# pmd_final.net
KiCad netlist of a schematic drawn in EAGLE
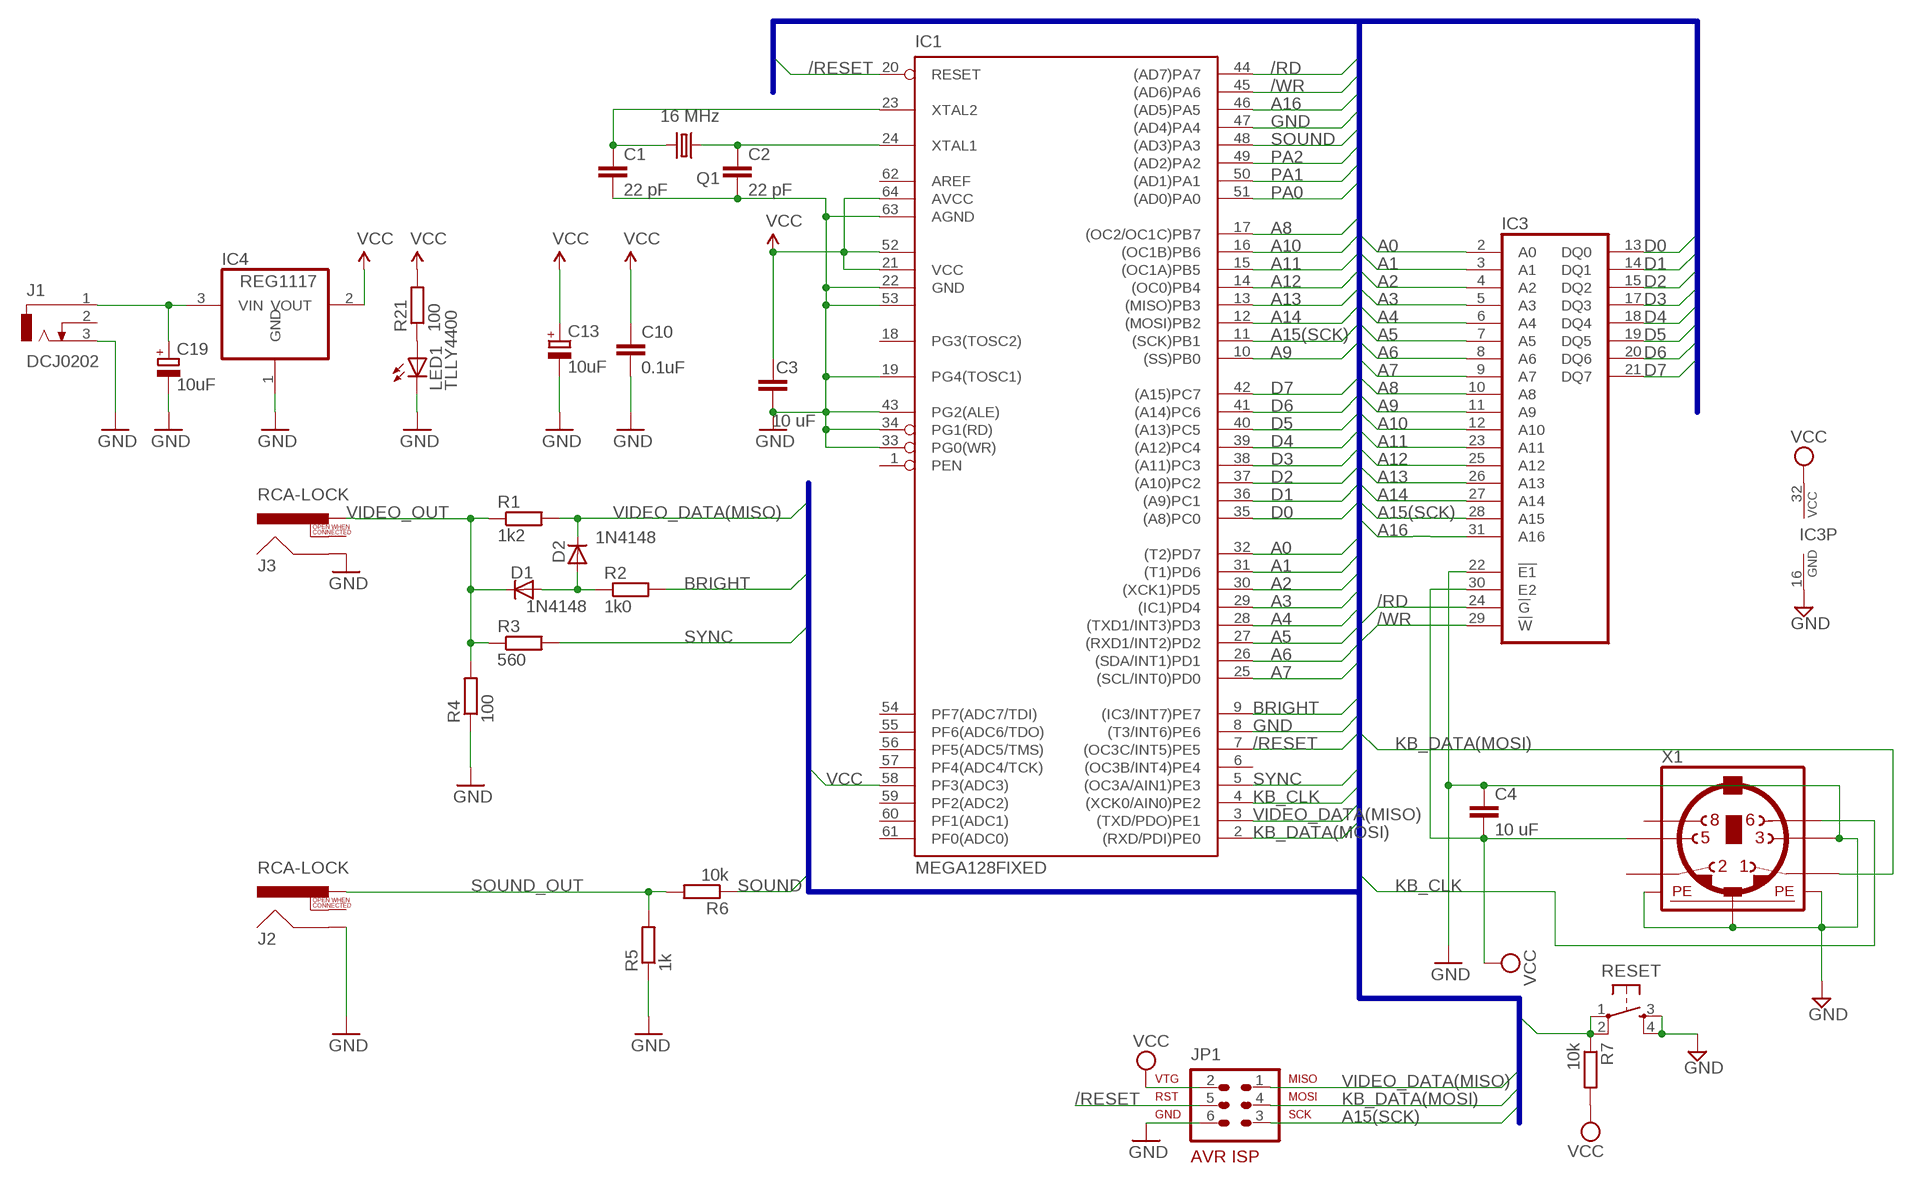
[diagram p0: schematic, sheet 1]

(export (version "E")
  (design (tool "Eeschema 10.0.6"))
  (components
    (comp (ref "C1")
      (value "22 pF")
      (footprint "eagle-import:C0805")
      (libsource (lib "eagle-import") (part "C-EUC0805"))
    )
    (comp (ref "C2")
      (value "22 pF")
      (footprint "eagle-import:C0805")
      (libsource (lib "eagle-import") (part "C-EUC0805"))
    )
    (comp (ref "C3")
      (value "10 uF")
      (footprint "eagle-import:C0805")
      (libsource (lib "eagle-import") (part "C-EUC0805"))
    )
    (comp (ref "C4")
      (value "10 uF")
      (footprint "eagle-import:C0805")
      (libsource (lib "eagle-import") (part "C-EUC0805"))
    )
    (comp (ref "C10")
      (value "0.1uF")
      (footprint "eagle-import:C0805")
      (libsource (lib "eagle-import") (part "C-EUC0805"))
    )
    (comp (ref "C13")
      (value "10uF")
      (footprint "eagle-import:E2,5-5")
      (libsource (lib "eagle-import") (part "CPOL-EUE2.5-5"))
    )
    (comp (ref "C19")
      (value "10uF")
      (footprint "eagle-import:E2,5-5")
      (libsource (lib "eagle-import") (part "CPOL-EUE2.5-5"))
    )
    (comp (ref "D1")
      (value "1N4148")
      (footprint "eagle-import:MINIMELF")
      (libsource (lib "eagle-import") (part "DIODE-MINIMELF"))
    )
    (comp (ref "D2")
      (value "1N4148")
      (footprint "eagle-import:MINIMELF")
      (libsource (lib "eagle-import") (part "DIODE-MINIMELF"))
    )
    (comp (ref "IC1")
      (value "MEGA128FIXED")
      (footprint "eagle-import:TQFP64_14X14MM")
      (libsource (lib "eagle-import") (part "MEGA128FIXED"))
    )
    (comp (ref "IC3")
      (value "MCM6226AULTRAWIDE")
      (footprint "eagle-import:SOP32L")
      (libsource (lib "eagle-import") (part "MCM6226AULTRAWIDE"))
    )
    (comp (ref "IC4")
      (value "REG1117")
      (footprint "eagle-import:SOT223")
      (libsource (lib "eagle-import") (part "REG1117"))
    )
    (comp (ref "J1")
      (value "DCJ0202")
      (footprint "eagle-import:DCJ0202")
      (libsource (lib "eagle-import") (part "DCJ0202"))
    )
    (comp (ref "J2")
      (value "RCA-LOCK")
      (footprint "eagle-import:RCA_LOCK")
      (libsource (lib "eagle-import") (part "RCA-LOCK"))
    )
    (comp (ref "J3")
      (value "RCA-LOCK")
      (footprint "eagle-import:RCA_LOCK")
      (libsource (lib "eagle-import") (part "RCA-LOCK"))
    )
    (comp (ref "JP1")
      (value "AVR-ISP-6R")
      (footprint "eagle-import:AVR-ISP-6R")
      (libsource (lib "eagle-import") (part "AVR-ISP-6R"))
    )
    (comp (ref "LED1")
      (value "TLLY4400")
      (footprint "eagle-import:LED3MM")
      (fields (field (name "MF") "VISHAY SEMICONDUCTOR"))
      (libsource (lib "eagle-import") (part "TLLY4400"))
    )
    (comp (ref "Q1")
      (value "16 MHz")
      (footprint "eagle-import:HC49UP")
      (libsource (lib "eagle-import") (part "CRYSTALHC49UP"))
    )
    (comp (ref "R1")
      (value "1k2")
      (footprint "eagle-import:R0805")
      (libsource (lib "eagle-import") (part "R-EU_R0805"))
    )
    (comp (ref "R2")
      (value "1k0")
      (footprint "eagle-import:R0805")
      (libsource (lib "eagle-import") (part "R-EU_R0805"))
    )
    (comp (ref "R3")
      (value "560")
      (footprint "eagle-import:R0805")
      (libsource (lib "eagle-import") (part "R-EU_R0805"))
    )
    (comp (ref "R4")
      (value "100")
      (footprint "eagle-import:R0805")
      (libsource (lib "eagle-import") (part "R-EU_R0805"))
    )
    (comp (ref "R5")
      (value "1k")
      (footprint "eagle-import:R0805")
      (libsource (lib "eagle-import") (part "R-EU_R0805"))
    )
    (comp (ref "R6")
      (value "10k")
      (footprint "eagle-import:R0805")
      (libsource (lib "eagle-import") (part "R-EU_R0805"))
    )
    (comp (ref "R7")
      (value "10k")
      (footprint "eagle-import:R0805")
      (libsource (lib "eagle-import") (part "R-EU_R0805"))
    )
    (comp (ref "R21")
      (value "100")
      (footprint "eagle-import:R0805")
      (libsource (lib "eagle-import") (part "R-EU_R0805"))
    )
    (comp (ref "RESET")
      (value "RESET")
      (footprint "eagle-import:TACTILE-PTH")
      (libsource (lib "eagle-import") (part "TAC_SWITCHPTH"))
    )
    (comp (ref "X1")
      (value "MINI_DIN_6")
      (footprint "eagle-import:M_DIN6")
      (libsource (lib "eagle-import") (part "MINI_DIN_6"))
    )
  )
  (nets
    (net (code "1") (name "/A0") (class "Default")
      (node (ref "IC1") (pin "32") (pinfunction "(T2)PD7_32") (pintype "bidirectional"))
      (node (ref "IC3") (pin "2") (pinfunction "A0_2") (pintype "input"))
    )
    (net (code "2") (name "/A1") (class "Default")
      (node (ref "IC1") (pin "31") (pinfunction "(T1)PD6_31") (pintype "bidirectional"))
      (node (ref "IC3") (pin "3") (pinfunction "A1_3") (pintype "input"))
    )
    (net (code "3") (name "/A2") (class "Default")
      (node (ref "IC1") (pin "30") (pinfunction "(XCK1)PD5_30") (pintype "bidirectional"))
      (node (ref "IC3") (pin "4") (pinfunction "A2_4") (pintype "input"))
    )
    (net (code "4") (name "/A3") (class "Default")
      (node (ref "IC1") (pin "29") (pinfunction "(IC1)PD4_29") (pintype "bidirectional"))
      (node (ref "IC3") (pin "5") (pinfunction "A3_5") (pintype "input"))
    )
    (net (code "5") (name "/A4") (class "Default")
      (node (ref "IC1") (pin "28") (pinfunction "(TXD1/INT3)PD3_28") (pintype "bidirectional"))
      (node (ref "IC3") (pin "6") (pinfunction "A4_6") (pintype "input"))
    )
    (net (code "6") (name "/A5") (class "Default")
      (node (ref "IC1") (pin "27") (pinfunction "(RXD1/INT2)PD2_27") (pintype "bidirectional"))
      (node (ref "IC3") (pin "7") (pinfunction "A5_7") (pintype "input"))
    )
    (net (code "7") (name "/A6") (class "Default")
      (node (ref "IC1") (pin "26") (pinfunction "(SDA/INT1)PD1_26") (pintype "bidirectional"))
      (node (ref "IC3") (pin "8") (pinfunction "A6_8") (pintype "input"))
    )
    (net (code "8") (name "/A7") (class "Default")
      (node (ref "IC1") (pin "25") (pinfunction "(SCL/INT0)PD0_25") (pintype "bidirectional"))
      (node (ref "IC3") (pin "9") (pinfunction "A7_9") (pintype "input"))
    )
    (net (code "9") (name "/A8") (class "Default")
      (node (ref "IC1") (pin "17") (pinfunction "(OC2/OC1C)PB7_17") (pintype "bidirectional"))
      (node (ref "IC3") (pin "10") (pinfunction "A8_10") (pintype "input"))
    )
    (net (code "10") (name "/A9") (class "Default")
      (node (ref "IC1") (pin "10") (pinfunction "(SS)PB0_10") (pintype "bidirectional"))
      (node (ref "IC3") (pin "11") (pinfunction "A9_11") (pintype "input"))
    )
    (net (code "11") (name "/A10") (class "Default")
      (node (ref "IC1") (pin "16") (pinfunction "(OC1B)PB6_16") (pintype "bidirectional"))
      (node (ref "IC3") (pin "12") (pinfunction "A10_12") (pintype "input"))
    )
    (net (code "12") (name "/A11") (class "Default")
      (node (ref "IC1") (pin "15") (pinfunction "(OC1A)PB5_15") (pintype "bidirectional"))
      (node (ref "IC3") (pin "23") (pinfunction "A11_23") (pintype "input"))
    )
    (net (code "13") (name "/A12") (class "Default")
      (node (ref "IC1") (pin "14") (pinfunction "(OC0)PB4_14") (pintype "bidirectional"))
      (node (ref "IC3") (pin "25") (pinfunction "A12_25") (pintype "input"))
    )
    (net (code "14") (name "/A13") (class "Default")
      (node (ref "IC1") (pin "13") (pinfunction "(MISO)PB3_13") (pintype "bidirectional"))
      (node (ref "IC3") (pin "26") (pinfunction "A13_26") (pintype "input"))
    )
    (net (code "15") (name "/A14") (class "Default")
      (node (ref "IC1") (pin "12") (pinfunction "(MOSI)PB2_12") (pintype "bidirectional"))
      (node (ref "IC3") (pin "27") (pinfunction "A14_27") (pintype "input"))
    )
    (net (code "16") (name "/A15(SCK)") (class "Default")
      (node (ref "IC1") (pin "11") (pinfunction "(SCK)PB1_11") (pintype "bidirectional"))
      (node (ref "IC3") (pin "28") (pinfunction "A15_28") (pintype "input"))
      (node (ref "JP1") (pin "3") (pinfunction "3_3") (pintype "passive"))
    )
    (net (code "17") (name "/A16") (class "Default")
      (node (ref "IC1") (pin "46") (pinfunction "(AD5)PA5_46") (pintype "bidirectional"))
      (node (ref "IC3") (pin "31") (pinfunction "A16_31") (pintype "input"))
    )
    (net (code "18") (name "/BRIGHT") (class "Default")
      (node (ref "IC1") (pin "9") (pinfunction "(IC3/INT7)PE7_9") (pintype "bidirectional"))
      (node (ref "R2") (pin "2") (pinfunction "2_2") (pintype "passive"))
    )
    (net (code "19") (name "/D0") (class "Default")
      (node (ref "IC1") (pin "35") (pinfunction "(A8)PC0_35") (pintype "output"))
      (node (ref "IC3") (pin "13") (pinfunction "DQ0_13") (pintype "bidirectional"))
    )
    (net (code "20") (name "/D1") (class "Default")
      (node (ref "IC1") (pin "36") (pinfunction "(A9)PC1_36") (pintype "output"))
      (node (ref "IC3") (pin "14") (pinfunction "DQ1_14") (pintype "bidirectional"))
    )
    (net (code "21") (name "/D2") (class "Default")
      (node (ref "IC1") (pin "37") (pinfunction "(A10)PC2_37") (pintype "output"))
      (node (ref "IC3") (pin "15") (pinfunction "DQ2_15") (pintype "bidirectional"))
    )
    (net (code "22") (name "/D3") (class "Default")
      (node (ref "IC1") (pin "38") (pinfunction "(A11)PC3_38") (pintype "output"))
      (node (ref "IC3") (pin "17") (pinfunction "DQ3_17") (pintype "bidirectional"))
    )
    (net (code "23") (name "/D4") (class "Default")
      (node (ref "IC1") (pin "39") (pinfunction "(A12)PC4_39") (pintype "output"))
      (node (ref "IC3") (pin "18") (pinfunction "DQ4_18") (pintype "bidirectional"))
    )
    (net (code "24") (name "/D5") (class "Default")
      (node (ref "IC1") (pin "40") (pinfunction "(A13)PC5_40") (pintype "output"))
      (node (ref "IC3") (pin "19") (pinfunction "DQ5_19") (pintype "bidirectional"))
    )
    (net (code "25") (name "/D6") (class "Default")
      (node (ref "IC1") (pin "41") (pinfunction "(A14)PC6_41") (pintype "output"))
      (node (ref "IC3") (pin "20") (pinfunction "DQ6_20") (pintype "bidirectional"))
    )
    (net (code "26") (name "/D7") (class "Default")
      (node (ref "IC1") (pin "42") (pinfunction "(A15)PC7_42") (pintype "output"))
      (node (ref "IC3") (pin "21") (pinfunction "DQ7_21") (pintype "bidirectional"))
    )
    (net (code "27") (name "/KB_CLK") (class "Default")
      (node (ref "IC1") (pin "4") (pinfunction "(XCK0/AIN0)PE2_4") (pintype "bidirectional"))
      (node (ref "X1") (pin "6") (pinfunction "6_6") (pintype "passive"))
    )
    (net (code "28") (name "/KB_DATA(MOSI)") (class "Default")
      (node (ref "IC1") (pin "2") (pinfunction "(RXD/PDI)PE0_2") (pintype "bidirectional"))
      (node (ref "JP1") (pin "4") (pinfunction "4_4") (pintype "passive"))
      (node (ref "X1") (pin "1") (pinfunction "1_1") (pintype "passive"))
    )
    (net (code "29") (name "/PA0") (class "Default")
      (node (ref "IC1") (pin "51") (pinfunction "(AD0)PA0_51") (pintype "bidirectional"))
    )
    (net (code "30") (name "/PA1") (class "Default")
      (node (ref "IC1") (pin "50") (pinfunction "(AD1)PA1_50") (pintype "bidirectional"))
    )
    (net (code "31") (name "/PA2") (class "Default")
      (node (ref "IC1") (pin "49") (pinfunction "(AD2)PA2_49") (pintype "bidirectional"))
    )
    (net (code "32") (name "/SOUND") (class "Default")
      (node (ref "IC1") (pin "48") (pinfunction "(AD3)PA3_48") (pintype "bidirectional"))
      (node (ref "R6") (pin "1") (pinfunction "1_1") (pintype "passive"))
    )
    (net (code "33") (name "/SOUND_OUT") (class "Default")
      (node (ref "J2") (pin "PIN") (pinfunction "PIN_PIN") (pintype "bidirectional"))
      (node (ref "R5") (pin "2") (pinfunction "2_2") (pintype "passive"))
      (node (ref "R6") (pin "2") (pinfunction "2_2") (pintype "passive"))
    )
    (net (code "34") (name "/SYNC") (class "Default")
      (node (ref "IC1") (pin "5") (pinfunction "(OC3A/AIN1)PE3_5") (pintype "bidirectional"))
      (node (ref "R3") (pin "2") (pinfunction "2_2") (pintype "passive"))
    )
    (net (code "35") (name "/VIDEO_DATA(MISO)") (class "Default")
      (node (ref "D2") (pin "C") (pinfunction "C_C") (pintype "passive"))
      (node (ref "IC1") (pin "3") (pinfunction "(TXD/PDO)PE1_3") (pintype "bidirectional"))
      (node (ref "JP1") (pin "1") (pinfunction "1_1") (pintype "passive"))
      (node (ref "R1") (pin "2") (pinfunction "2_2") (pintype "passive"))
    )
    (net (code "36") (name "/VIDEO_OUT") (class "Default")
      (node (ref "D1") (pin "C") (pinfunction "C_C") (pintype "passive"))
      (node (ref "J3") (pin "PIN") (pinfunction "PIN_PIN") (pintype "bidirectional"))
      (node (ref "R1") (pin "1") (pinfunction "1_1") (pintype "passive"))
      (node (ref "R3") (pin "1") (pinfunction "1_1") (pintype "passive"))
      (node (ref "R4") (pin "2") (pinfunction "2_2") (pintype "passive"))
    )
    (net (code "37") (name "/{slash}RD") (class "Default")
      (node (ref "IC1") (pin "44") (pinfunction "(AD7)PA7_44") (pintype "bidirectional"))
      (node (ref "IC3") (pin "24") (pinfunction "~{G}_24") (pintype "input"))
    )
    (net (code "38") (name "/{slash}RESET") (class "Default")
      (node (ref "IC1") (pin "20") (pinfunction "RESET_20") (pintype "input"))
      (node (ref "IC1") (pin "7") (pinfunction "(OC3C/INT5)PE5_7") (pintype "bidirectional"))
      (node (ref "JP1") (pin "5") (pinfunction "5_5") (pintype "passive"))
      (node (ref "R7") (pin "1") (pinfunction "1_1") (pintype "passive"))
      (node (ref "RESET") (pin "1") (pinfunction "1_1") (pintype "passive"))
      (node (ref "RESET") (pin "2") (pinfunction "2_2") (pintype "passive"))
    )
    (net (code "39") (name "/{slash}WR") (class "Default")
      (node (ref "IC1") (pin "45") (pinfunction "(AD6)PA6_45") (pintype "bidirectional"))
      (node (ref "IC3") (pin "29") (pinfunction "~{W}_29") (pintype "input"))
    )
    (net (code "40") (name "GND") (class "Default")
      (node (ref "C1") (pin "2") (pinfunction "2_2") (pintype "passive"))
      (node (ref "C10") (pin "2") (pinfunction "2_2") (pintype "passive"))
      (node (ref "C13") (pin "-") (pinfunction "-_-") (pintype "passive"))
      (node (ref "C19") (pin "-") (pinfunction "-_-") (pintype "passive"))
      (node (ref "C2") (pin "2") (pinfunction "2_2") (pintype "passive"))
      (node (ref "C3") (pin "1") (pinfunction "1_1") (pintype "passive"))
      (node (ref "C4") (pin "1") (pinfunction "1_1") (pintype "passive"))
      (node (ref "IC1") (pin "19") (pinfunction "PG4(TOSC1)_19") (pintype "bidirectional"))
      (node (ref "IC1") (pin "22") (pinfunction "GND_22") (pintype "power_in"))
      (node (ref "IC1") (pin "33") (pinfunction "PG0(WR)_33") (pintype "bidirectional"))
      (node (ref "IC1") (pin "34") (pinfunction "PG1(RD)_34") (pintype "bidirectional"))
      (node (ref "IC1") (pin "43") (pinfunction "PG2(ALE)_43") (pintype "bidirectional"))
      (node (ref "IC1") (pin "47") (pinfunction "(AD4)PA4_47") (pintype "bidirectional"))
      (node (ref "IC1") (pin "53") (pinfunction "GND1_53") (pintype "power_in"))
      (node (ref "IC1") (pin "63") (pinfunction "AGND_63") (pintype "bidirectional"))
      (node (ref "IC1") (pin "8") (pinfunction "(T3/INT6)PE6_8") (pintype "bidirectional"))
      (node (ref "IC3") (pin "16") (pinfunction "GND_16") (pintype "power_in"))
      (node (ref "IC3") (pin "22") (pinfunction "~{E1}_22") (pintype "input"))
      (node (ref "IC4") (pin "1") (pinfunction "GND_1") (pintype "power_in"))
      (node (ref "J1") (pin "3") (pinfunction "3_3") (pintype "passive"))
      (node (ref "J2") (pin "SHELL") (pinfunction "SHELL_SHELL") (pintype "bidirectional"))
      (node (ref "J3") (pin "SHELL") (pinfunction "SHELL_SHELL") (pintype "bidirectional"))
      (node (ref "JP1") (pin "6") (pinfunction "6_6") (pintype "passive"))
      (node (ref "LED1") (pin "K") (pinfunction "C_K") (pintype "passive"))
      (node (ref "R4") (pin "1") (pinfunction "1_1") (pintype "passive"))
      (node (ref "R5") (pin "1") (pinfunction "1_1") (pintype "passive"))
      (node (ref "RESET") (pin "3") (pinfunction "3_3") (pintype "passive"))
      (node (ref "RESET") (pin "4") (pinfunction "4_4") (pintype "passive"))
      (node (ref "X1") (pin "3") (pinfunction "3_3") (pintype "passive"))
      (node (ref "X1") (pin "SH1") (pinfunction "PE1_SH1") (pintype "power_in"))
      (node (ref "X1") (pin "SH2") (pinfunction "PE2_SH2") (pintype "power_in"))
      (node (ref "X1") (pin "SH3") (pinfunction "PE3_SH3") (pintype "power_in"))
    )
    (net (code "41") (name "Net-(D1-PadA)") (class "Default")
      (node (ref "D1") (pin "A") (pinfunction "A_A") (pintype "passive"))
      (node (ref "D2") (pin "A") (pinfunction "A_A") (pintype "passive"))
      (node (ref "R2") (pin "1") (pinfunction "1_1") (pintype "passive"))
    )
    (net (code "42") (name "Net-(IC1-XTAL1)") (class "Default")
      (node (ref "C2") (pin "1") (pinfunction "1_1") (pintype "passive"))
      (node (ref "IC1") (pin "24") (pinfunction "XTAL1_24") (pintype "bidirectional"))
      (node (ref "Q1") (pin "1") (pinfunction "1_1") (pintype "passive"))
    )
    (net (code "43") (name "Net-(IC1-XTAL2)") (class "Default")
      (node (ref "C1") (pin "1") (pinfunction "1_1") (pintype "passive"))
      (node (ref "IC1") (pin "23") (pinfunction "XTAL2_23") (pintype "bidirectional"))
      (node (ref "Q1") (pin "2") (pinfunction "2_2") (pintype "passive"))
    )
    (net (code "44") (name "Net-(IC4-VIN)") (class "Default")
      (node (ref "C19") (pin "+") (pinfunction "+_+") (pintype "passive"))
      (node (ref "IC4") (pin "3") (pinfunction "VIN_3") (pintype "input"))
      (node (ref "J1") (pin "1") (pinfunction "1_1") (pintype "passive"))
    )
    (net (code "45") (name "Net-(LED1-PadA)") (class "Default")
      (node (ref "LED1") (pin "A") (pinfunction "A_A") (pintype "passive"))
      (node (ref "R21") (pin "1") (pinfunction "1_1") (pintype "passive"))
    )
    (net (code "46") (name "VCC") (class "Default")
      (node (ref "C10") (pin "1") (pinfunction "1_1") (pintype "passive"))
      (node (ref "C13") (pin "+") (pinfunction "+_+") (pintype "passive"))
      (node (ref "C3") (pin "2") (pinfunction "2_2") (pintype "passive"))
      (node (ref "C4") (pin "2") (pinfunction "2_2") (pintype "passive"))
      (node (ref "IC1") (pin "21") (pinfunction "VCC_21") (pintype "power_in"))
      (node (ref "IC1") (pin "52") (pinfunction "VCC1_52") (pintype "power_in"))
      (node (ref "IC1") (pin "58") (pinfunction "PF3(ADC3)_58") (pintype "input"))
      (node (ref "IC1") (pin "64") (pinfunction "AVCC_64") (pintype "bidirectional"))
      (node (ref "IC3") (pin "30") (pinfunction "E2_30") (pintype "input"))
      (node (ref "IC3") (pin "32") (pinfunction "VCC_32") (pintype "power_in"))
      (node (ref "IC4") (pin "2") (pinfunction "VOUT_2") (pintype "output"))
      (node (ref "JP1") (pin "2") (pinfunction "2_2") (pintype "passive"))
      (node (ref "R21") (pin "2") (pinfunction "2_2") (pintype "passive"))
      (node (ref "R7") (pin "2") (pinfunction "2_2") (pintype "passive"))
      (node (ref "X1") (pin "5") (pinfunction "5_5") (pintype "passive"))
    )
    (net (code "47") (name "unconnected-(IC1-(OC3B{slash}INT4)PE4-Pad6)") (class "Default")
      (node (ref "IC1") (pin "6") (pinfunction "(OC3B/INT4)PE4_6") (pintype "bidirectional"))
    )
    (net (code "48") (name "unconnected-(IC1-AREF-Pad62)") (class "Default")
      (node (ref "IC1") (pin "62") (pinfunction "AREF_62") (pintype "bidirectional"))
    )
    (net (code "49") (name "unconnected-(IC1-PEN-Pad1)") (class "Default")
      (node (ref "IC1") (pin "1") (pinfunction "PEN_1") (pintype "input"))
    )
    (net (code "50") (name "unconnected-(IC1-PF0(ADC0)-Pad61)") (class "Default")
      (node (ref "IC1") (pin "61") (pinfunction "PF0(ADC0)_61") (pintype "input"))
    )
    (net (code "51") (name "unconnected-(IC1-PF1(ADC1)-Pad60)") (class "Default")
      (node (ref "IC1") (pin "60") (pinfunction "PF1(ADC1)_60") (pintype "input"))
    )
    (net (code "52") (name "unconnected-(IC1-PF2(ADC2)-Pad59)") (class "Default")
      (node (ref "IC1") (pin "59") (pinfunction "PF2(ADC2)_59") (pintype "input"))
    )
    (net (code "53") (name "unconnected-(IC1-PF4(ADC4{slash}TCK)-Pad57)") (class "Default")
      (node (ref "IC1") (pin "57") (pinfunction "PF4(ADC4/TCK)_57") (pintype "input"))
    )
    (net (code "54") (name "unconnected-(IC1-PF5(ADC5{slash}TMS)-Pad56)") (class "Default")
      (node (ref "IC1") (pin "56") (pinfunction "PF5(ADC5/TMS)_56") (pintype "input"))
    )
    (net (code "55") (name "unconnected-(IC1-PF6(ADC6{slash}TDO)-Pad55)") (class "Default")
      (node (ref "IC1") (pin "55") (pinfunction "PF6(ADC6/TDO)_55") (pintype "input"))
    )
    (net (code "56") (name "unconnected-(IC1-PF7(ADC7{slash}TDI)-Pad54)") (class "Default")
      (node (ref "IC1") (pin "54") (pinfunction "PF7(ADC7/TDI)_54") (pintype "input"))
    )
    (net (code "57") (name "unconnected-(IC1-PG3(TOSC2)-Pad18)") (class "Default")
      (node (ref "IC1") (pin "18") (pinfunction "PG3(TOSC2)_18") (pintype "bidirectional"))
    )
    (net (code "58") (name "unconnected-(J1-Pad2)") (class "Default")
      (node (ref "J1") (pin "2") (pinfunction "2_2") (pintype "passive"))
    )
    (net (code "59") (name "unconnected-(J2-PadSWITCH)") (class "Default")
      (node (ref "J2") (pin "SWITCH") (pinfunction "SWITCH_SWITCH") (pintype "bidirectional"))
    )
    (net (code "60") (name "unconnected-(J3-PadSWITCH)") (class "Default")
      (node (ref "J3") (pin "SWITCH") (pinfunction "SWITCH_SWITCH") (pintype "bidirectional"))
    )
    (net (code "61") (name "unconnected-(X1-Pad2)") (class "Default")
      (node (ref "X1") (pin "2") (pinfunction "2_2") (pintype "passive"))
    )
    (net (code "62") (name "unconnected-(X1-Pad8)") (class "Default")
      (node (ref "X1") (pin "8") (pinfunction "8_8") (pintype "passive"))
    )
  )
)
